# untitled.net
KiCad netlist of a schematic drawn in EAGLE
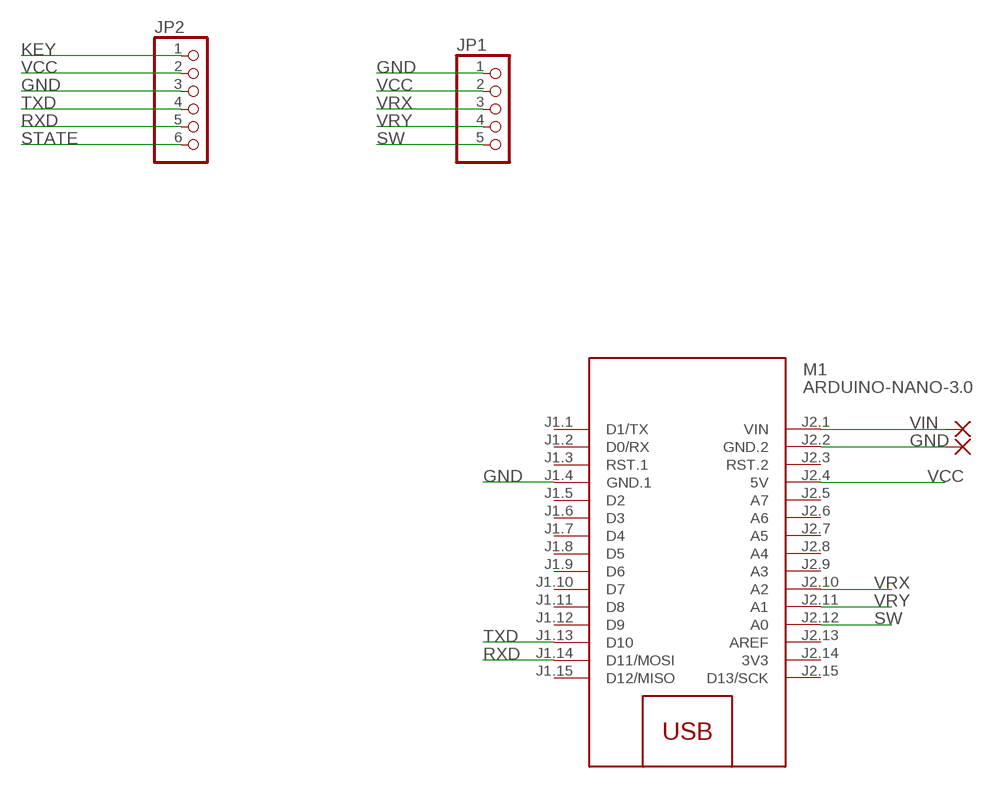
[diagram p0: schematic, sheet 1]

(export (version "E")
  (design (tool "Eeschema 10.0.6"))
  (components
    (comp (ref "JP1")
      (value "PINHD-1X5")
      (footprint "eagle-import:1X05")
      (libsource (lib "eagle-import") (part "PINHD-1X5"))
    )
    (comp (ref "JP2")
      (value "PINHD-1X6")
      (footprint "eagle-import:1X06")
      (libsource (lib "eagle-import") (part "PINHD-1X6"))
    )
    (comp (ref "M1")
      (value "ARDUINO-NANO-3.0")
      (footprint "eagle-import:ARDUINO-NANO-3.0")
      (libsource (lib "eagle-import") (part "ARDUINO-NANO-3.0"))
    )
    (comp (ref "PAD1")
      (value "WIREPADSMD5-2,5")
      (footprint "eagle-import:5-2,5")
      (libsource (lib "eagle-import") (part "WIREPADSMD5-2,5"))
    )
    (comp (ref "PAD2")
      (value "WIREPADSMD5-2,5")
      (footprint "eagle-import:5-2,5")
      (libsource (lib "eagle-import") (part "WIREPADSMD5-2,5"))
    )
  )
  (nets
    (net (code "1") (name "/3V3") (class "Default")
      (node (ref "M1") (pin "J2.14") (pinfunction "3V3_J2.14") (pintype "power_in"))
    )
    (net (code "2") (name "/GND") (class "Default")
      (node (ref "JP1") (pin "1") (pinfunction "1_1") (pintype "passive"))
      (node (ref "JP2") (pin "3") (pinfunction "3_3") (pintype "passive"))
      (node (ref "M1") (pin "J1.4") (pinfunction "GND.1_J1.4") (pintype "power_in"))
      (node (ref "M1") (pin "J2.2") (pinfunction "GND.2_J2.2") (pintype "power_in"))
      (node (ref "PAD2") (pin "1") (pinfunction "P_1") (pintype "passive"))
    )
    (net (code "3") (name "/KEY") (class "Default")
      (node (ref "JP2") (pin "1") (pinfunction "1_1") (pintype "passive"))
    )
    (net (code "4") (name "/RXD") (class "Default")
      (node (ref "JP2") (pin "5") (pinfunction "5_5") (pintype "passive"))
      (node (ref "M1") (pin "J1.14") (pinfunction "D11/MOSI_J1.14") (pintype "bidirectional"))
    )
    (net (code "5") (name "/STATE") (class "Default")
      (node (ref "JP2") (pin "6") (pinfunction "6_6") (pintype "passive"))
    )
    (net (code "6") (name "/SW") (class "Default")
      (node (ref "JP1") (pin "5") (pinfunction "5_5") (pintype "passive"))
      (node (ref "M1") (pin "J2.12") (pinfunction "A0_J2.12") (pintype "bidirectional"))
    )
    (net (code "7") (name "/TXD") (class "Default")
      (node (ref "JP2") (pin "4") (pinfunction "4_4") (pintype "passive"))
      (node (ref "M1") (pin "J1.13") (pinfunction "D10_J1.13") (pintype "bidirectional"))
    )
    (net (code "8") (name "/VCC") (class "Default")
      (node (ref "JP1") (pin "2") (pinfunction "2_2") (pintype "passive"))
      (node (ref "JP2") (pin "2") (pinfunction "2_2") (pintype "passive"))
      (node (ref "M1") (pin "J2.4") (pinfunction "5V_J2.4") (pintype "power_in"))
    )
    (net (code "9") (name "/VIN") (class "Default")
      (node (ref "M1") (pin "J2.1") (pinfunction "VIN_J2.1") (pintype "power_in"))
      (node (ref "PAD1") (pin "1") (pinfunction "P_1") (pintype "passive"))
    )
    (net (code "10") (name "/VRX") (class "Default")
      (node (ref "JP1") (pin "3") (pinfunction "3_3") (pintype "passive"))
      (node (ref "M1") (pin "J2.10") (pinfunction "A2_J2.10") (pintype "bidirectional"))
    )
    (net (code "11") (name "/VRY") (class "Default")
      (node (ref "JP1") (pin "4") (pinfunction "4_4") (pintype "passive"))
      (node (ref "M1") (pin "J2.11") (pinfunction "A1_J2.11") (pintype "bidirectional"))
    )
    (net (code "12") (name "unconnected-(M1-A3-PadJ2.9)") (class "Default")
      (node (ref "M1") (pin "J2.9") (pinfunction "A3_J2.9") (pintype "bidirectional"))
    )
    (net (code "13") (name "unconnected-(M1-A4-PadJ2.8)") (class "Default")
      (node (ref "M1") (pin "J2.8") (pinfunction "A4_J2.8") (pintype "bidirectional"))
    )
    (net (code "14") (name "unconnected-(M1-A5-PadJ2.7)") (class "Default")
      (node (ref "M1") (pin "J2.7") (pinfunction "A5_J2.7") (pintype "bidirectional"))
    )
    (net (code "15") (name "unconnected-(M1-A6-PadJ2.6)") (class "Default")
      (node (ref "M1") (pin "J2.6") (pinfunction "A6_J2.6") (pintype "bidirectional"))
    )
    (net (code "16") (name "unconnected-(M1-A7-PadJ2.5)") (class "Default")
      (node (ref "M1") (pin "J2.5") (pinfunction "A7_J2.5") (pintype "bidirectional"))
    )
    (net (code "17") (name "unconnected-(M1-AREF-PadJ2.13)") (class "Default")
      (node (ref "M1") (pin "J2.13") (pinfunction "AREF_J2.13") (pintype "bidirectional"))
    )
    (net (code "18") (name "unconnected-(M1-D0{slash}RX-PadJ1.2)") (class "Default")
      (node (ref "M1") (pin "J1.2") (pinfunction "D0/RX_J1.2") (pintype "bidirectional"))
    )
    (net (code "19") (name "unconnected-(M1-D1{slash}TX-PadJ1.1)") (class "Default")
      (node (ref "M1") (pin "J1.1") (pinfunction "D1/TX_J1.1") (pintype "bidirectional"))
    )
    (net (code "20") (name "unconnected-(M1-D2-PadJ1.5)") (class "Default")
      (node (ref "M1") (pin "J1.5") (pinfunction "D2_J1.5") (pintype "bidirectional"))
    )
    (net (code "21") (name "unconnected-(M1-D3-PadJ1.6)") (class "Default")
      (node (ref "M1") (pin "J1.6") (pinfunction "D3_J1.6") (pintype "bidirectional"))
    )
    (net (code "22") (name "unconnected-(M1-D4-PadJ1.7)") (class "Default")
      (node (ref "M1") (pin "J1.7") (pinfunction "D4_J1.7") (pintype "bidirectional"))
    )
    (net (code "23") (name "unconnected-(M1-D5-PadJ1.8)") (class "Default")
      (node (ref "M1") (pin "J1.8") (pinfunction "D5_J1.8") (pintype "bidirectional"))
    )
    (net (code "24") (name "unconnected-(M1-D6-PadJ1.9)") (class "Default")
      (node (ref "M1") (pin "J1.9") (pinfunction "D6_J1.9") (pintype "bidirectional"))
    )
    (net (code "25") (name "unconnected-(M1-D7-PadJ1.10)") (class "Default")
      (node (ref "M1") (pin "J1.10") (pinfunction "D7_J1.10") (pintype "bidirectional"))
    )
    (net (code "26") (name "unconnected-(M1-D8-PadJ1.11)") (class "Default")
      (node (ref "M1") (pin "J1.11") (pinfunction "D8_J1.11") (pintype "bidirectional"))
    )
    (net (code "27") (name "unconnected-(M1-D9-PadJ1.12)") (class "Default")
      (node (ref "M1") (pin "J1.12") (pinfunction "D9_J1.12") (pintype "bidirectional"))
    )
    (net (code "28") (name "unconnected-(M1-D12{slash}MISO-PadJ1.15)") (class "Default")
      (node (ref "M1") (pin "J1.15") (pinfunction "D12/MISO_J1.15") (pintype "bidirectional"))
    )
    (net (code "29") (name "unconnected-(M1-D13{slash}SCK-PadJ2.15)") (class "Default")
      (node (ref "M1") (pin "J2.15") (pinfunction "D13/SCK_J2.15") (pintype "bidirectional"))
    )
    (net (code "30") (name "unconnected-(M1-RST.1-PadJ1.3)") (class "Default")
      (node (ref "M1") (pin "J1.3") (pinfunction "RST.1_J1.3") (pintype "bidirectional"))
    )
    (net (code "31") (name "unconnected-(M1-RST.2-PadJ2.3)") (class "Default")
      (node (ref "M1") (pin "J2.3") (pinfunction "RST.2_J2.3") (pintype "bidirectional"))
    )
  )
)
